# CrackberryPi_1_0_6_2_ir.net
KiCad netlist of a schematic drawn in EAGLE
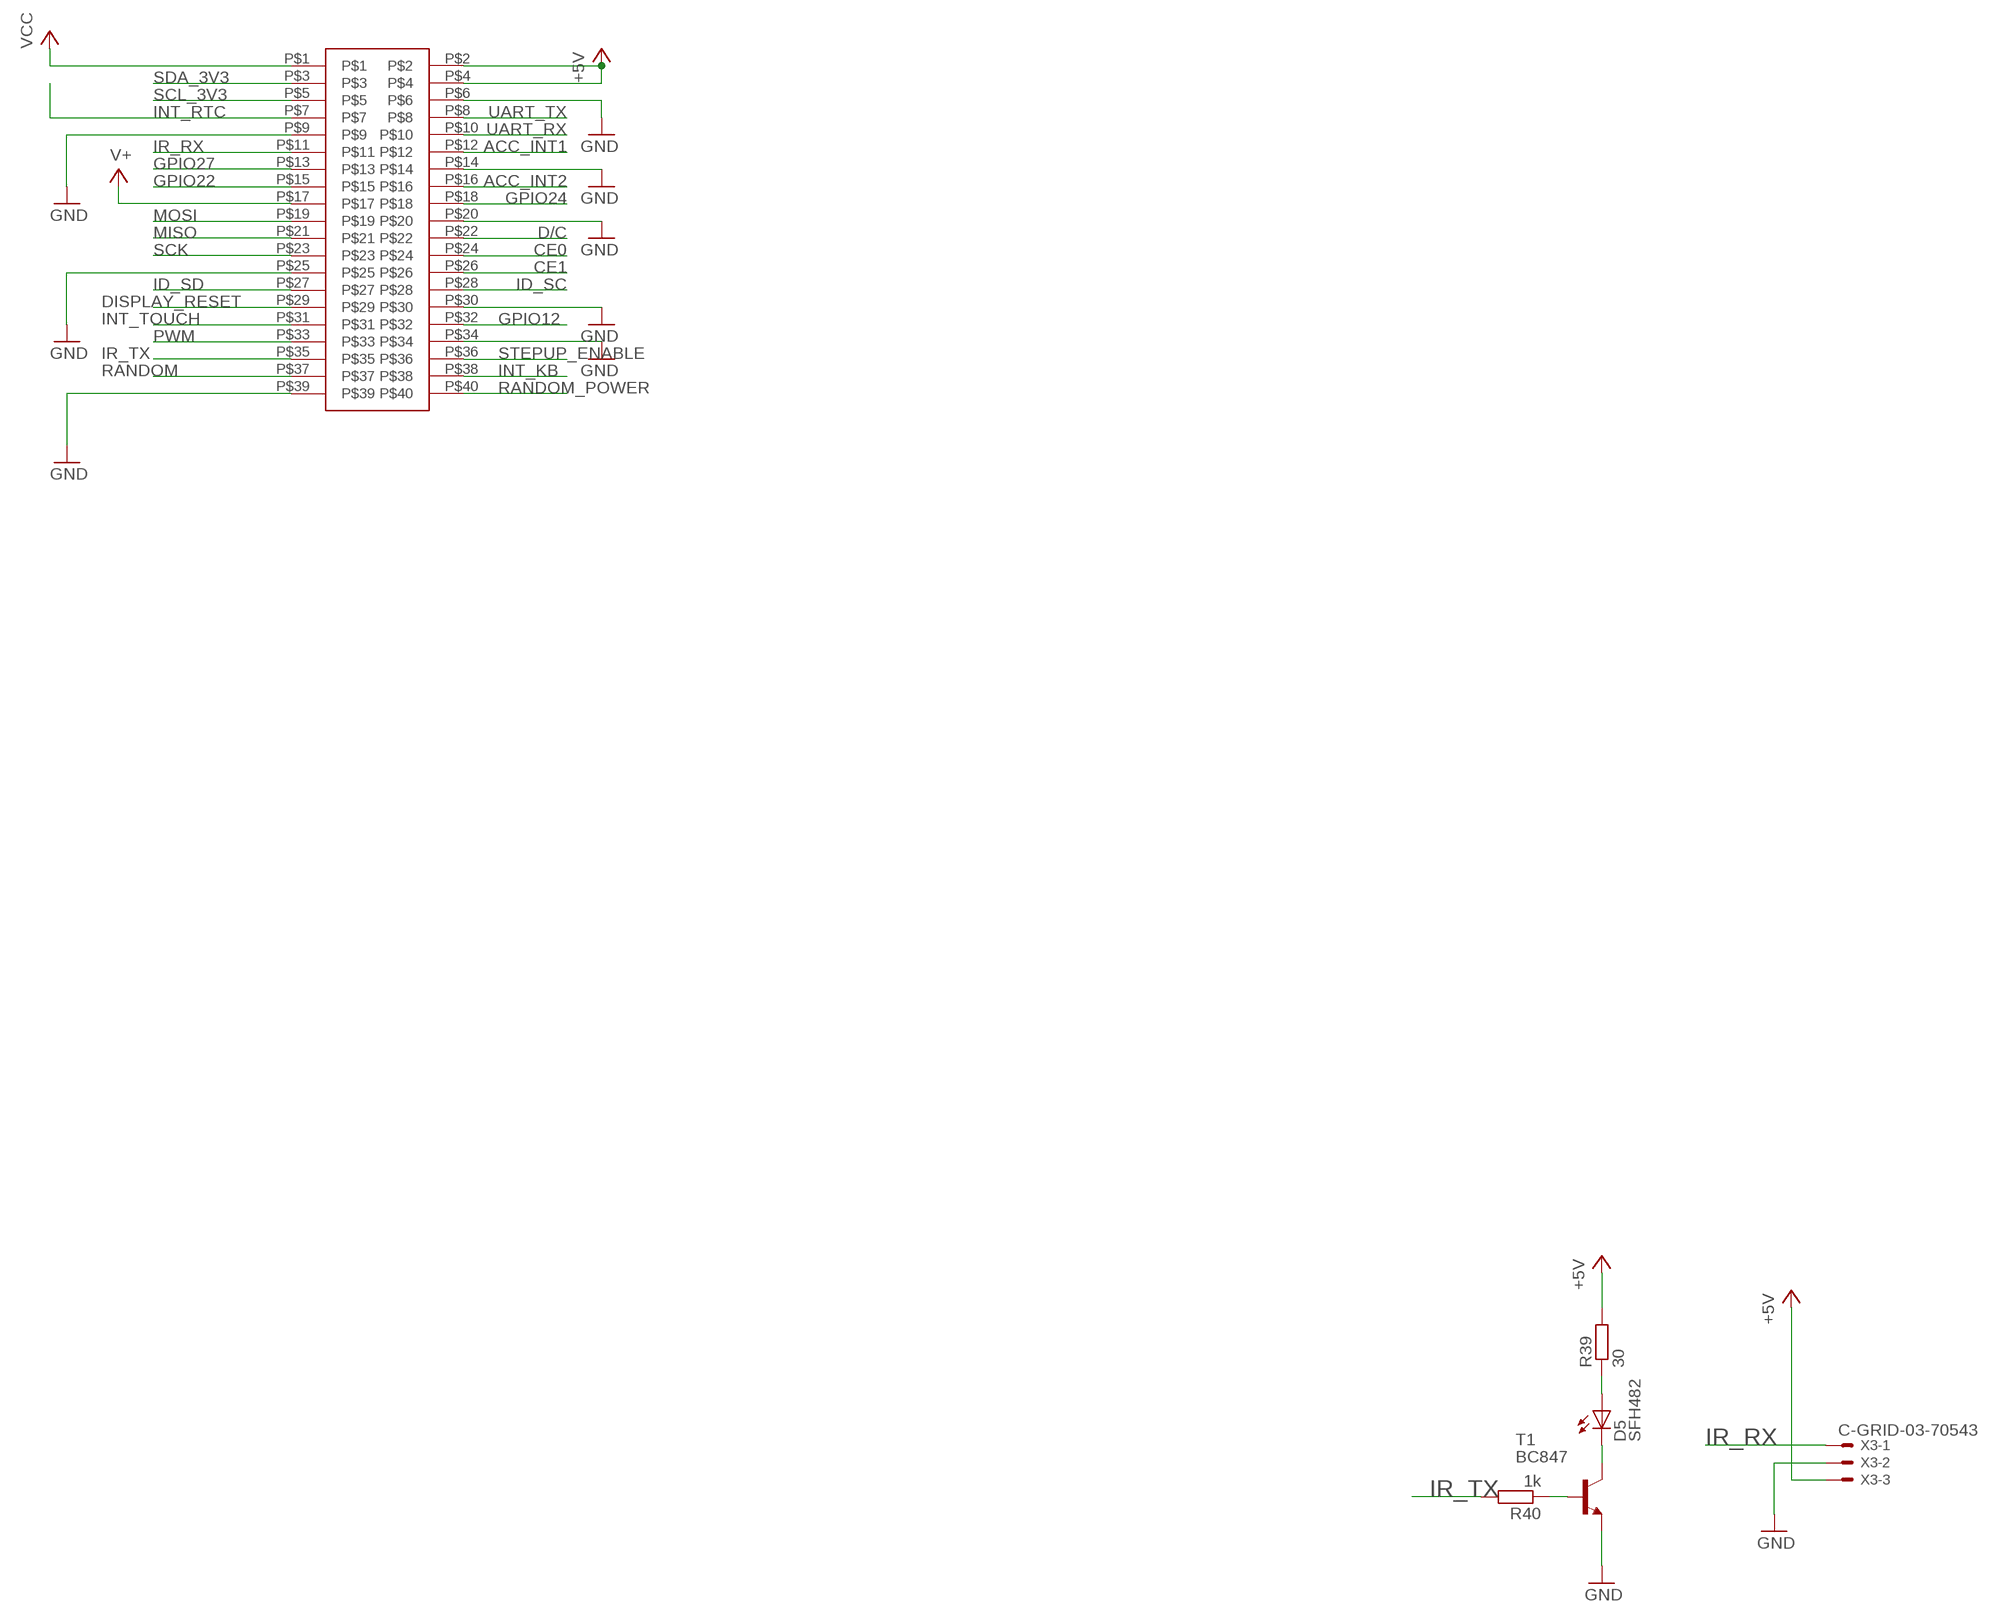
[diagram p0: schematic, sheet 1]

(export (version "E")
  (design (tool "Eeschema 10.0.6"))
  (components
    (comp (ref "D5")
      (value "SFH482")
      (footprint "eagle-import:SFH482")
      (libsource (lib "eagle-import") (part "SFH482"))
    )
    (comp (ref "R39")
      (value "30")
      (footprint "eagle-import:R0603")
      (libsource (lib "eagle-import") (part "R-EU_R0603"))
    )
    (comp (ref "R40")
      (value "1k")
      (footprint "eagle-import:R0603")
      (libsource (lib "eagle-import") (part "R-EU_R0603"))
    )
    (comp (ref "T1")
      (value "BC847")
      (footprint "eagle-import:SOT23")
      (libsource (lib "eagle-import") (part "BC847"))
    )
    (comp (ref "U$11")
      (value "HEADER")
      (footprint "eagle-import:20X2")
      (libsource (lib "eagle-import") (part "HEADER"))
    )
    (comp (ref "X3")
      (value "C-GRID-03-70543")
      (footprint "eagle-import:70543-03")
      (libsource (lib "eagle-import") (part "C-GRID-03-70543"))
    )
  )
  (nets
    (net (code "1") (name "+5V") (class "Default")
      (node (ref "R39") (pin "2") (pinfunction "2_2") (pintype "passive"))
      (node (ref "U$11") (pin "P$2") (pinfunction "P$2_P$2") (pintype "bidirectional"))
      (node (ref "U$11") (pin "P$4") (pinfunction "P$4_P$4") (pintype "bidirectional"))
      (node (ref "X3") (pin "3") (pinfunction "S_3") (pintype "passive"))
    )
    (net (code "2") (name "/ACC_INT1") (class "Default")
      (node (ref "U$11") (pin "P$12") (pinfunction "P$12_P$12") (pintype "bidirectional"))
    )
    (net (code "3") (name "/ACC_INT2") (class "Default")
      (node (ref "U$11") (pin "P$16") (pinfunction "P$16_P$16") (pintype "bidirectional"))
    )
    (net (code "4") (name "/CE0") (class "Default")
      (node (ref "U$11") (pin "P$24") (pinfunction "P$24_P$24") (pintype "bidirectional"))
    )
    (net (code "5") (name "/CE1") (class "Default")
      (node (ref "U$11") (pin "P$26") (pinfunction "P$26_P$26") (pintype "bidirectional"))
    )
    (net (code "6") (name "/DISPLAY_RESET") (class "Default")
      (node (ref "U$11") (pin "P$29") (pinfunction "P$29_P$29") (pintype "bidirectional"))
    )
    (net (code "7") (name "/D{slash}C") (class "Default")
      (node (ref "U$11") (pin "P$22") (pinfunction "P$22_P$22") (pintype "bidirectional"))
    )
    (net (code "8") (name "/GPIO12") (class "Default")
      (node (ref "U$11") (pin "P$32") (pinfunction "P$32_P$32") (pintype "bidirectional"))
    )
    (net (code "9") (name "/GPIO22") (class "Default")
      (node (ref "U$11") (pin "P$15") (pinfunction "P$15_P$15") (pintype "bidirectional"))
    )
    (net (code "10") (name "/GPIO24") (class "Default")
      (node (ref "U$11") (pin "P$18") (pinfunction "P$18_P$18") (pintype "bidirectional"))
    )
    (net (code "11") (name "/GPIO27") (class "Default")
      (node (ref "U$11") (pin "P$13") (pinfunction "P$13_P$13") (pintype "bidirectional"))
    )
    (net (code "12") (name "/ID_SC") (class "Default")
      (node (ref "U$11") (pin "P$28") (pinfunction "P$28_P$28") (pintype "bidirectional"))
    )
    (net (code "13") (name "/ID_SD") (class "Default")
      (node (ref "U$11") (pin "P$27") (pinfunction "P$27_P$27") (pintype "bidirectional"))
    )
    (net (code "14") (name "/INT_KB") (class "Default")
      (node (ref "U$11") (pin "P$38") (pinfunction "P$38_P$38") (pintype "bidirectional"))
    )
    (net (code "15") (name "/INT_RTC") (class "Default")
      (node (ref "U$11") (pin "P$7") (pinfunction "P$7_P$7") (pintype "bidirectional"))
    )
    (net (code "16") (name "/INT_TOUCH") (class "Default")
      (node (ref "U$11") (pin "P$31") (pinfunction "P$31_P$31") (pintype "bidirectional"))
    )
    (net (code "17") (name "/IR_RX") (class "Default")
      (node (ref "U$11") (pin "P$11") (pinfunction "P$11_P$11") (pintype "bidirectional"))
      (node (ref "X3") (pin "1") (pinfunction "S_1") (pintype "passive"))
    )
    (net (code "18") (name "/IR_TX") (class "Default")
      (node (ref "R40") (pin "2") (pinfunction "2_2") (pintype "passive"))
      (node (ref "U$11") (pin "P$35") (pinfunction "P$35_P$35") (pintype "bidirectional"))
    )
    (net (code "19") (name "/MISO") (class "Default")
      (node (ref "U$11") (pin "P$21") (pinfunction "P$21_P$21") (pintype "bidirectional"))
    )
    (net (code "20") (name "/MOSI") (class "Default")
      (node (ref "U$11") (pin "P$19") (pinfunction "P$19_P$19") (pintype "bidirectional"))
    )
    (net (code "21") (name "/PWM") (class "Default")
      (node (ref "U$11") (pin "P$33") (pinfunction "P$33_P$33") (pintype "bidirectional"))
    )
    (net (code "22") (name "/RANDOM") (class "Default")
      (node (ref "U$11") (pin "P$37") (pinfunction "P$37_P$37") (pintype "bidirectional"))
    )
    (net (code "23") (name "/RANDOM_POWER") (class "Default")
      (node (ref "U$11") (pin "P$40") (pinfunction "P$40_P$40") (pintype "bidirectional"))
    )
    (net (code "24") (name "/SCK") (class "Default")
      (node (ref "U$11") (pin "P$23") (pinfunction "P$23_P$23") (pintype "bidirectional"))
    )
    (net (code "25") (name "/SCL_3V3") (class "Default")
      (node (ref "U$11") (pin "P$5") (pinfunction "P$5_P$5") (pintype "bidirectional"))
    )
    (net (code "26") (name "/SDA_3V3") (class "Default")
      (node (ref "U$11") (pin "P$3") (pinfunction "P$3_P$3") (pintype "bidirectional"))
    )
    (net (code "27") (name "/STEPUP_ENABLE") (class "Default")
      (node (ref "U$11") (pin "P$36") (pinfunction "P$36_P$36") (pintype "bidirectional"))
    )
    (net (code "28") (name "/UART_RX") (class "Default")
      (node (ref "U$11") (pin "P$10") (pinfunction "P$10_P$10") (pintype "bidirectional"))
    )
    (net (code "29") (name "/UART_TX") (class "Default")
      (node (ref "U$11") (pin "P$8") (pinfunction "P$8_P$8") (pintype "bidirectional"))
    )
    (net (code "30") (name "GND") (class "Default")
      (node (ref "T1") (pin "2") (pinfunction "E_2") (pintype "passive"))
      (node (ref "U$11") (pin "P$14") (pinfunction "P$14_P$14") (pintype "bidirectional"))
      (node (ref "U$11") (pin "P$20") (pinfunction "P$20_P$20") (pintype "bidirectional"))
      (node (ref "U$11") (pin "P$25") (pinfunction "P$25_P$25") (pintype "bidirectional"))
      (node (ref "U$11") (pin "P$30") (pinfunction "P$30_P$30") (pintype "bidirectional"))
      (node (ref "U$11") (pin "P$34") (pinfunction "P$34_P$34") (pintype "bidirectional"))
      (node (ref "U$11") (pin "P$39") (pinfunction "P$39_P$39") (pintype "bidirectional"))
      (node (ref "U$11") (pin "P$6") (pinfunction "P$6_P$6") (pintype "bidirectional"))
      (node (ref "U$11") (pin "P$9") (pinfunction "P$9_P$9") (pintype "bidirectional"))
      (node (ref "X3") (pin "2") (pinfunction "S_2") (pintype "passive"))
    )
    (net (code "31") (name "Net-(D5-C)") (class "Default")
      (node (ref "D5") (pin "K") (pinfunction "C_K") (pintype "passive"))
      (node (ref "T1") (pin "3") (pinfunction "C_3") (pintype "passive"))
    )
    (net (code "32") (name "Net-(D5-PadA)") (class "Default")
      (node (ref "D5") (pin "A") (pinfunction "A_A") (pintype "passive"))
      (node (ref "R39") (pin "1") (pinfunction "1_1") (pintype "passive"))
    )
    (net (code "33") (name "Net-(T1-B)") (class "Default")
      (node (ref "R40") (pin "1") (pinfunction "1_1") (pintype "passive"))
      (node (ref "T1") (pin "1") (pinfunction "B_1") (pintype "passive"))
    )
    (net (code "34") (name "V+") (class "Default")
      (node (ref "U$11") (pin "P$17") (pinfunction "P$17_P$17") (pintype "bidirectional"))
    )
    (net (code "35") (name "VCC") (class "Default")
      (node (ref "U$11") (pin "P$1") (pinfunction "P$1_P$1") (pintype "bidirectional"))
    )
  )
)
